# mini-keyboard.net
KiCad netlist of a schematic drawn in EAGLE
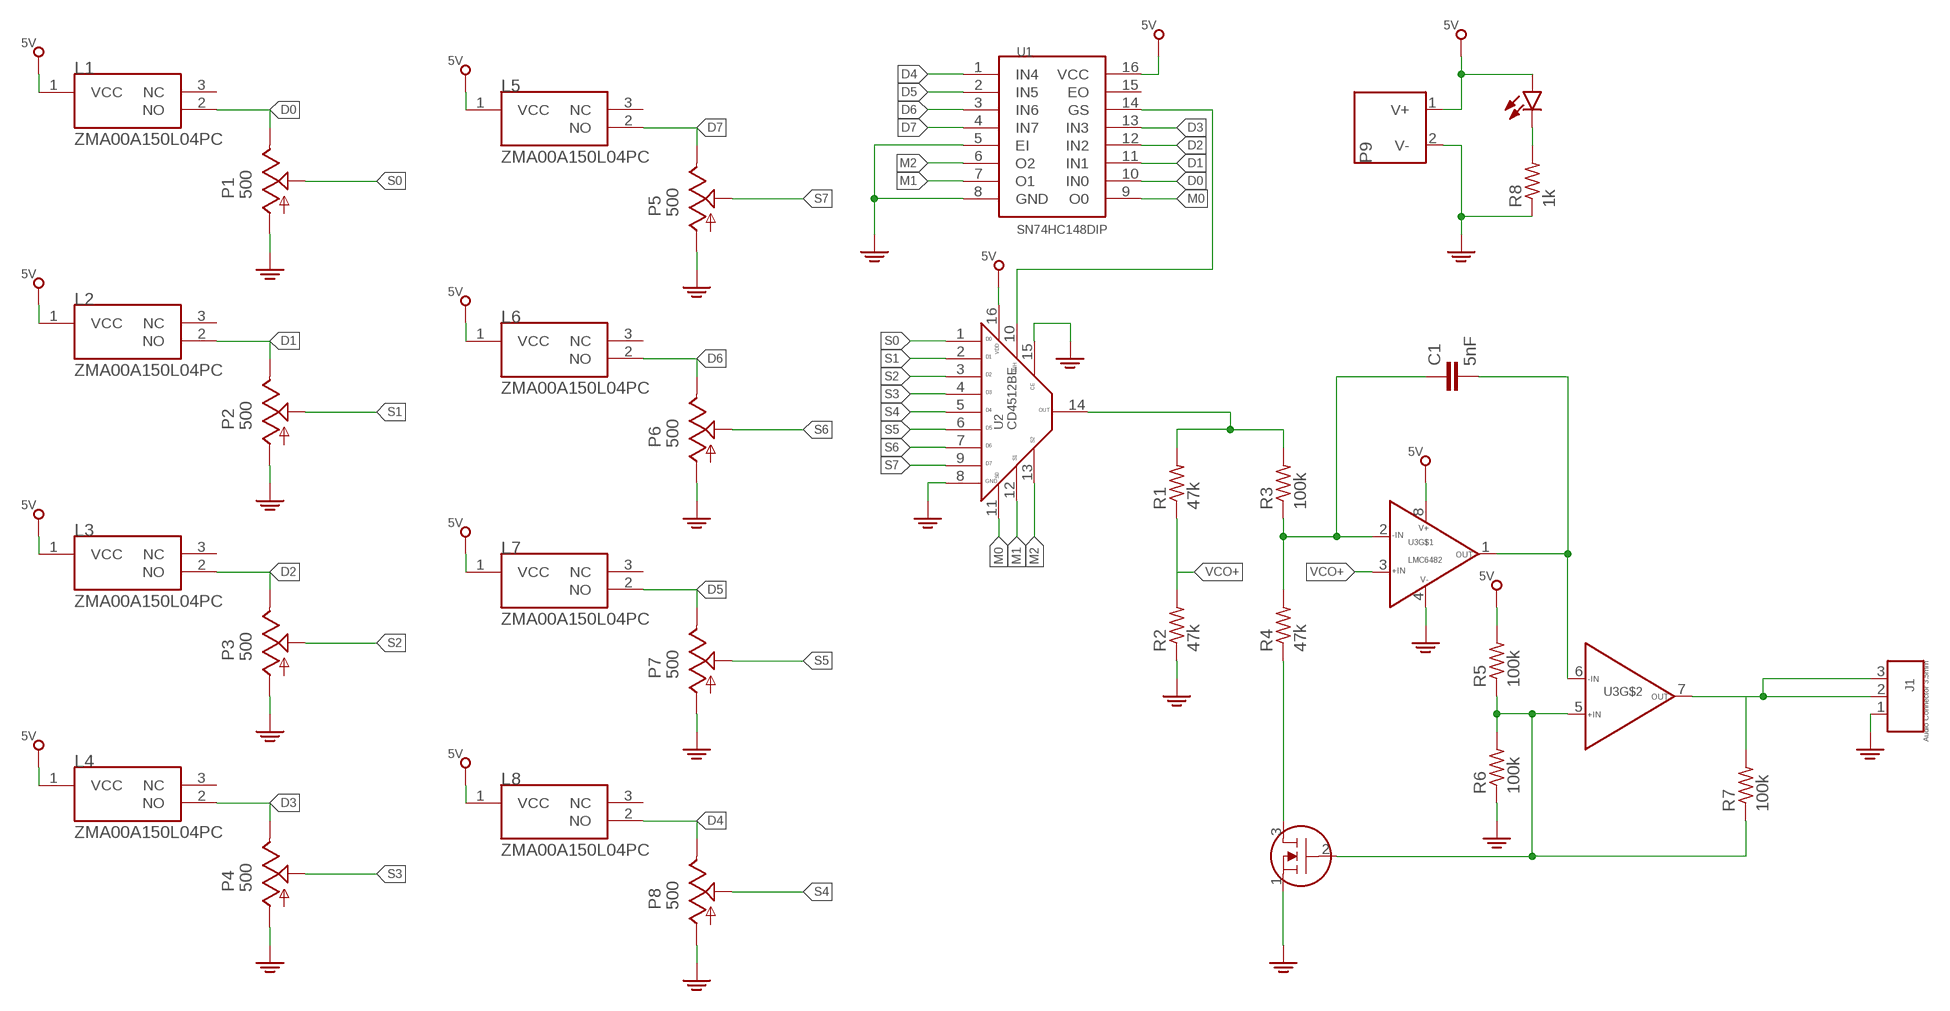
[diagram p0: schematic, sheet 1]

(export (version "E")
  (design (tool "Eeschema 10.0.6"))
  (components
    (comp (ref "C1")
      (value "5nF")
      (footprint "eagle-import:0603")
      (libsource (lib "eagle-import") (part "C0603"))
    )
    (comp (ref "J1")
      (value "SJ-3523-SMT")
      (footprint "eagle-import:SJ-352X-SMT")
      (libsource (lib "eagle-import") (part "SJ-3523-SMT"))
    )
    (comp (ref "L1")
      (value "ZMA00A150L04PC")
      (footprint "eagle-import:ZMA-LIMSWITCH")
      (libsource (lib "eagle-import") (part "ZMA00A150L04PC"))
    )
    (comp (ref "L2")
      (value "ZMA00A150L04PC")
      (footprint "eagle-import:ZMA-LIMSWITCH")
      (libsource (lib "eagle-import") (part "ZMA00A150L04PC"))
    )
    (comp (ref "L3")
      (value "ZMA00A150L04PC")
      (footprint "eagle-import:ZMA-LIMSWITCH")
      (libsource (lib "eagle-import") (part "ZMA00A150L04PC"))
    )
    (comp (ref "L4")
      (value "ZMA00A150L04PC")
      (footprint "eagle-import:ZMA-LIMSWITCH")
      (libsource (lib "eagle-import") (part "ZMA00A150L04PC"))
    )
    (comp (ref "L5")
      (value "ZMA00A150L04PC")
      (footprint "eagle-import:ZMA-LIMSWITCH")
      (libsource (lib "eagle-import") (part "ZMA00A150L04PC"))
    )
    (comp (ref "L6")
      (value "ZMA00A150L04PC")
      (footprint "eagle-import:ZMA-LIMSWITCH")
      (libsource (lib "eagle-import") (part "ZMA00A150L04PC"))
    )
    (comp (ref "L7")
      (value "ZMA00A150L04PC")
      (footprint "eagle-import:ZMA-LIMSWITCH")
      (libsource (lib "eagle-import") (part "ZMA00A150L04PC"))
    )
    (comp (ref "L8")
      (value "ZMA00A150L04PC")
      (footprint "eagle-import:ZMA-LIMSWITCH")
      (libsource (lib "eagle-import") (part "ZMA00A150L04PC"))
    )
    (comp (ref "P1")
      (value "500")
      (footprint "eagle-import:3214X")
      (libsource (lib "eagle-import") (part "POTSMD"))
    )
    (comp (ref "P2")
      (value "500")
      (footprint "eagle-import:3214X")
      (libsource (lib "eagle-import") (part "POTSMD"))
    )
    (comp (ref "P3")
      (value "500")
      (footprint "eagle-import:3214X")
      (libsource (lib "eagle-import") (part "POTSMD"))
    )
    (comp (ref "P4")
      (value "500")
      (footprint "eagle-import:3214X")
      (libsource (lib "eagle-import") (part "POTSMD"))
    )
    (comp (ref "P5")
      (value "500")
      (footprint "eagle-import:3214X")
      (libsource (lib "eagle-import") (part "POTSMD"))
    )
    (comp (ref "P6")
      (value "500")
      (footprint "eagle-import:3214X")
      (libsource (lib "eagle-import") (part "POTSMD"))
    )
    (comp (ref "P7")
      (value "500")
      (footprint "eagle-import:3214X")
      (libsource (lib "eagle-import") (part "POTSMD"))
    )
    (comp (ref "P8")
      (value "500")
      (footprint "eagle-import:3214X")
      (libsource (lib "eagle-import") (part "POTSMD"))
    )
    (comp (ref "P9")
      (value "SINGLE-LINE")
      (footprint "eagle-import:BARREL-SPFUN-BRBRD")
      (libsource (lib "eagle-import") (part "SINGLE-LINE"))
    )
    (comp (ref "PWR")
      (value "LED-STD")
      (footprint "eagle-import:0603")
      (libsource (lib "eagle-import") (part "LED-STD"))
    )
    (comp (ref "R1")
      (value "47k")
      (footprint "eagle-import:0603")
      (libsource (lib "eagle-import") (part "R0603"))
    )
    (comp (ref "R2")
      (value "47k")
      (footprint "eagle-import:0603")
      (libsource (lib "eagle-import") (part "R0603"))
    )
    (comp (ref "R3")
      (value "100k")
      (footprint "eagle-import:0603")
      (libsource (lib "eagle-import") (part "R0603"))
    )
    (comp (ref "R4")
      (value "47k")
      (footprint "eagle-import:0603")
      (libsource (lib "eagle-import") (part "R0603"))
    )
    (comp (ref "R5")
      (value "100k")
      (footprint "eagle-import:0603")
      (libsource (lib "eagle-import") (part "R0603"))
    )
    (comp (ref "R6")
      (value "100k")
      (footprint "eagle-import:0603")
      (libsource (lib "eagle-import") (part "R0603"))
    )
    (comp (ref "R7")
      (value "100k")
      (footprint "eagle-import:0603")
      (libsource (lib "eagle-import") (part "R0603"))
    )
    (comp (ref "R8")
      (value "1k")
      (footprint "eagle-import:0603")
      (libsource (lib "eagle-import") (part "R0603"))
    )
    (comp (ref "U1")
      (value "SN74HC148DIP")
      (footprint "eagle-import:PDIP-16")
      (libsource (lib "eagle-import") (part "SN74HC148DIP"))
    )
    (comp (ref "U2")
      (value "CD4512BE")
      (footprint "eagle-import:PDIP-16")
      (libsource (lib "eagle-import") (part "CD4512BE"))
    )
    (comp (ref "U3")
      (value "LMC6482")
      (footprint "eagle-import:DIL08")
      (libsource (lib "eagle-import") (part "LMC6482"))
    )
    (comp (ref "U23")
      (value "2N7000-G")
      (footprint "eagle-import:TO92-CBE")
      (libsource (lib "eagle-import") (part "2N7000-G"))
    )
  )
  (nets
    (net (code "1") (name "5V") (class "Default")
      (node (ref "L1") (pin "1") (pinfunction "VCC_1") (pintype "bidirectional"))
      (node (ref "L2") (pin "1") (pinfunction "VCC_1") (pintype "bidirectional"))
      (node (ref "L3") (pin "1") (pinfunction "VCC_1") (pintype "bidirectional"))
      (node (ref "L4") (pin "1") (pinfunction "VCC_1") (pintype "bidirectional"))
      (node (ref "L5") (pin "1") (pinfunction "VCC_1") (pintype "bidirectional"))
      (node (ref "L6") (pin "1") (pinfunction "VCC_1") (pintype "bidirectional"))
      (node (ref "L7") (pin "1") (pinfunction "VCC_1") (pintype "bidirectional"))
      (node (ref "L8") (pin "1") (pinfunction "VCC_1") (pintype "bidirectional"))
      (node (ref "P9") (pin "1") (pinfunction "V+_1") (pintype "bidirectional"))
      (node (ref "PWR") (pin "IN") (pinfunction "IN_IN") (pintype "bidirectional"))
      (node (ref "R5") (pin "2") (pinfunction "P$2_2") (pintype "bidirectional"))
      (node (ref "U1") (pin "16") (pinfunction "VCC_16") (pintype "bidirectional"))
      (node (ref "U2") (pin "16") (pinfunction "VDD_16") (pintype "power_in"))
      (node (ref "U3") (pin "8") (pinfunction "VCC_8") (pintype "bidirectional"))
    )
    (net (code "2") (name "D0") (class "Default")
      (node (ref "L1") (pin "2") (pinfunction "NO_2") (pintype "bidirectional"))
      (node (ref "P1") (pin "3") (pinfunction "E_3") (pintype "passive"))
      (node (ref "U1") (pin "10") (pinfunction "IN0_10") (pintype "bidirectional"))
    )
    (net (code "3") (name "D1") (class "Default")
      (node (ref "L2") (pin "2") (pinfunction "NO_2") (pintype "bidirectional"))
      (node (ref "P2") (pin "3") (pinfunction "E_3") (pintype "passive"))
      (node (ref "U1") (pin "11") (pinfunction "IN1_11") (pintype "bidirectional"))
    )
    (net (code "4") (name "D2") (class "Default")
      (node (ref "L3") (pin "2") (pinfunction "NO_2") (pintype "bidirectional"))
      (node (ref "P3") (pin "3") (pinfunction "E_3") (pintype "passive"))
      (node (ref "U1") (pin "12") (pinfunction "IN2_12") (pintype "bidirectional"))
    )
    (net (code "5") (name "D3") (class "Default")
      (node (ref "L4") (pin "2") (pinfunction "NO_2") (pintype "bidirectional"))
      (node (ref "P4") (pin "3") (pinfunction "E_3") (pintype "passive"))
      (node (ref "U1") (pin "13") (pinfunction "IN3_13") (pintype "bidirectional"))
    )
    (net (code "6") (name "D4") (class "Default")
      (node (ref "L8") (pin "2") (pinfunction "NO_2") (pintype "bidirectional"))
      (node (ref "P8") (pin "3") (pinfunction "E_3") (pintype "passive"))
      (node (ref "U1") (pin "1") (pinfunction "IN4_1") (pintype "bidirectional"))
    )
    (net (code "7") (name "D5") (class "Default")
      (node (ref "L7") (pin "2") (pinfunction "NO_2") (pintype "bidirectional"))
      (node (ref "P7") (pin "3") (pinfunction "E_3") (pintype "passive"))
      (node (ref "U1") (pin "2") (pinfunction "IN5_2") (pintype "bidirectional"))
    )
    (net (code "8") (name "D6") (class "Default")
      (node (ref "L6") (pin "2") (pinfunction "NO_2") (pintype "bidirectional"))
      (node (ref "P6") (pin "3") (pinfunction "E_3") (pintype "passive"))
      (node (ref "U1") (pin "3") (pinfunction "IN6_3") (pintype "bidirectional"))
    )
    (net (code "9") (name "D7") (class "Default")
      (node (ref "L5") (pin "2") (pinfunction "NO_2") (pintype "bidirectional"))
      (node (ref "P5") (pin "3") (pinfunction "E_3") (pintype "passive"))
      (node (ref "U1") (pin "4") (pinfunction "IN7_4") (pintype "bidirectional"))
    )
    (net (code "10") (name "GND") (class "Default")
      (node (ref "J1") (pin "1") (pinfunction "1_1") (pintype "bidirectional"))
      (node (ref "P1") (pin "1") (pinfunction "A_1") (pintype "passive"))
      (node (ref "P2") (pin "1") (pinfunction "A_1") (pintype "passive"))
      (node (ref "P3") (pin "1") (pinfunction "A_1") (pintype "passive"))
      (node (ref "P4") (pin "1") (pinfunction "A_1") (pintype "passive"))
      (node (ref "P5") (pin "1") (pinfunction "A_1") (pintype "passive"))
      (node (ref "P6") (pin "1") (pinfunction "A_1") (pintype "passive"))
      (node (ref "P7") (pin "1") (pinfunction "A_1") (pintype "passive"))
      (node (ref "P8") (pin "1") (pinfunction "A_1") (pintype "passive"))
      (node (ref "P9") (pin "2") (pinfunction "V-_2") (pintype "bidirectional"))
      (node (ref "R2") (pin "1") (pinfunction "P$1_1") (pintype "bidirectional"))
      (node (ref "R6") (pin "1") (pinfunction "P$1_1") (pintype "bidirectional"))
      (node (ref "R8") (pin "1") (pinfunction "P$1_1") (pintype "bidirectional"))
      (node (ref "U1") (pin "5") (pinfunction "EI_5") (pintype "bidirectional"))
      (node (ref "U1") (pin "8") (pinfunction "GND_8") (pintype "bidirectional"))
      (node (ref "U2") (pin "15") (pinfunction "DISABLE_15") (pintype "bidirectional"))
      (node (ref "U2") (pin "8") (pinfunction "GND_8") (pintype "power_in"))
      (node (ref "U23") (pin "1") (pinfunction "S_1") (pintype "bidirectional"))
      (node (ref "U3") (pin "4") (pinfunction "GND_4") (pintype "bidirectional"))
    )
    (net (code "11") (name "M0") (class "Default")
      (node (ref "U1") (pin "9") (pinfunction "O0_9") (pintype "bidirectional"))
      (node (ref "U2") (pin "11") (pinfunction "S0_11") (pintype "bidirectional"))
    )
    (net (code "12") (name "M1") (class "Default")
      (node (ref "U1") (pin "7") (pinfunction "O1_7") (pintype "bidirectional"))
      (node (ref "U2") (pin "12") (pinfunction "S1_12") (pintype "bidirectional"))
    )
    (net (code "13") (name "M2") (class "Default")
      (node (ref "U1") (pin "6") (pinfunction "O2_6") (pintype "bidirectional"))
      (node (ref "U2") (pin "13") (pinfunction "S2_13") (pintype "bidirectional"))
    )
    (net (code "14") (name "Net-(R1-P$2)") (class "Default")
      (node (ref "R1") (pin "2") (pinfunction "P$2_2") (pintype "bidirectional"))
      (node (ref "R3") (pin "2") (pinfunction "P$2_2") (pintype "bidirectional"))
      (node (ref "U2") (pin "14") (pinfunction "OUT_14") (pintype "bidirectional"))
    )
    (net (code "15") (name "Net-(R3-P$1)") (class "Default")
      (node (ref "C1") (pin "1") (pinfunction "1_1") (pintype "passive"))
      (node (ref "R3") (pin "1") (pinfunction "P$1_1") (pintype "bidirectional"))
      (node (ref "R4") (pin "2") (pinfunction "P$2_2") (pintype "bidirectional"))
      (node (ref "U3") (pin "2") (pinfunction "-INA_2") (pintype "bidirectional"))
    )
    (net (code "16") (name "Net-(R4-P$1)") (class "Default")
      (node (ref "R4") (pin "1") (pinfunction "P$1_1") (pintype "bidirectional"))
      (node (ref "U23") (pin "3") (pinfunction "D_3") (pintype "bidirectional"))
    )
    (net (code "17") (name "Net-(R5-P$1)") (class "Default")
      (node (ref "R5") (pin "1") (pinfunction "P$1_1") (pintype "bidirectional"))
      (node (ref "R6") (pin "2") (pinfunction "P$2_2") (pintype "bidirectional"))
      (node (ref "R7") (pin "1") (pinfunction "P$1_1") (pintype "bidirectional"))
      (node (ref "U23") (pin "2") (pinfunction "G_2") (pintype "bidirectional"))
      (node (ref "U3") (pin "5") (pinfunction "+INB_5") (pintype "bidirectional"))
    )
    (net (code "18") (name "Net-(R7-P$2)") (class "Default")
      (node (ref "J1") (pin "2") (pinfunction "2_2") (pintype "bidirectional"))
      (node (ref "J1") (pin "3") (pinfunction "3_3") (pintype "bidirectional"))
      (node (ref "R7") (pin "2") (pinfunction "P$2_2") (pintype "bidirectional"))
      (node (ref "U3") (pin "7") (pinfunction "OUTB_7") (pintype "bidirectional"))
    )
    (net (code "19") (name "Net-(R8-P$2)") (class "Default")
      (node (ref "PWR") (pin "OUT") (pinfunction "OUT_OUT") (pintype "bidirectional"))
      (node (ref "R8") (pin "2") (pinfunction "P$2_2") (pintype "bidirectional"))
    )
    (net (code "20") (name "Net-(U1-GS)") (class "Default")
      (node (ref "U1") (pin "14") (pinfunction "GS_14") (pintype "bidirectional"))
      (node (ref "U2") (pin "10") (pinfunction "INHIBIT_10") (pintype "bidirectional"))
    )
    (net (code "21") (name "Net-(U3A-OUTA)") (class "Default")
      (node (ref "C1") (pin "2") (pinfunction "2_2") (pintype "passive"))
      (node (ref "U3") (pin "1") (pinfunction "OUTA_1") (pintype "bidirectional"))
      (node (ref "U3") (pin "6") (pinfunction "-INB_6") (pintype "bidirectional"))
    )
    (net (code "22") (name "S0") (class "Default")
      (node (ref "P1") (pin "2") (pinfunction "S_2") (pintype "passive"))
      (node (ref "U2") (pin "1") (pinfunction "D0_1") (pintype "bidirectional"))
    )
    (net (code "23") (name "S1") (class "Default")
      (node (ref "P2") (pin "2") (pinfunction "S_2") (pintype "passive"))
      (node (ref "U2") (pin "2") (pinfunction "D1_2") (pintype "bidirectional"))
    )
    (net (code "24") (name "S2") (class "Default")
      (node (ref "P3") (pin "2") (pinfunction "S_2") (pintype "passive"))
      (node (ref "U2") (pin "3") (pinfunction "D2_3") (pintype "bidirectional"))
    )
    (net (code "25") (name "S3") (class "Default")
      (node (ref "P4") (pin "2") (pinfunction "S_2") (pintype "passive"))
      (node (ref "U2") (pin "4") (pinfunction "D3_4") (pintype "bidirectional"))
    )
    (net (code "26") (name "S4") (class "Default")
      (node (ref "P8") (pin "2") (pinfunction "S_2") (pintype "passive"))
      (node (ref "U2") (pin "5") (pinfunction "D4_5") (pintype "bidirectional"))
    )
    (net (code "27") (name "S5") (class "Default")
      (node (ref "P7") (pin "2") (pinfunction "S_2") (pintype "passive"))
      (node (ref "U2") (pin "6") (pinfunction "D5_6") (pintype "bidirectional"))
    )
    (net (code "28") (name "S6") (class "Default")
      (node (ref "P6") (pin "2") (pinfunction "S_2") (pintype "passive"))
      (node (ref "U2") (pin "7") (pinfunction "D6_7") (pintype "bidirectional"))
    )
    (net (code "29") (name "S7") (class "Default")
      (node (ref "P5") (pin "2") (pinfunction "S_2") (pintype "passive"))
      (node (ref "U2") (pin "9") (pinfunction "D7_9") (pintype "bidirectional"))
    )
    (net (code "30") (name "VCO+") (class "Default")
      (node (ref "R1") (pin "1") (pinfunction "P$1_1") (pintype "bidirectional"))
      (node (ref "R2") (pin "2") (pinfunction "P$2_2") (pintype "bidirectional"))
      (node (ref "U3") (pin "3") (pinfunction "+INA_3") (pintype "bidirectional"))
    )
    (net (code "31") (name "unconnected-(L1-NC-Pad3)") (class "Default")
      (node (ref "L1") (pin "3") (pinfunction "NC_3") (pintype "bidirectional"))
    )
    (net (code "32") (name "unconnected-(L2-NC-Pad3)") (class "Default")
      (node (ref "L2") (pin "3") (pinfunction "NC_3") (pintype "bidirectional"))
    )
    (net (code "33") (name "unconnected-(L3-NC-Pad3)") (class "Default")
      (node (ref "L3") (pin "3") (pinfunction "NC_3") (pintype "bidirectional"))
    )
    (net (code "34") (name "unconnected-(L4-NC-Pad3)") (class "Default")
      (node (ref "L4") (pin "3") (pinfunction "NC_3") (pintype "bidirectional"))
    )
    (net (code "35") (name "unconnected-(L5-NC-Pad3)") (class "Default")
      (node (ref "L5") (pin "3") (pinfunction "NC_3") (pintype "bidirectional"))
    )
    (net (code "36") (name "unconnected-(L6-NC-Pad3)") (class "Default")
      (node (ref "L6") (pin "3") (pinfunction "NC_3") (pintype "bidirectional"))
    )
    (net (code "37") (name "unconnected-(L7-NC-Pad3)") (class "Default")
      (node (ref "L7") (pin "3") (pinfunction "NC_3") (pintype "bidirectional"))
    )
    (net (code "38") (name "unconnected-(L8-NC-Pad3)") (class "Default")
      (node (ref "L8") (pin "3") (pinfunction "NC_3") (pintype "bidirectional"))
    )
    (net (code "39") (name "unconnected-(U1-EO-Pad15)") (class "Default")
      (node (ref "U1") (pin "15") (pinfunction "EO_15") (pintype "bidirectional"))
    )
  )
)
